# avr.net
KiCad netlist of a schematic drawn in EAGLE
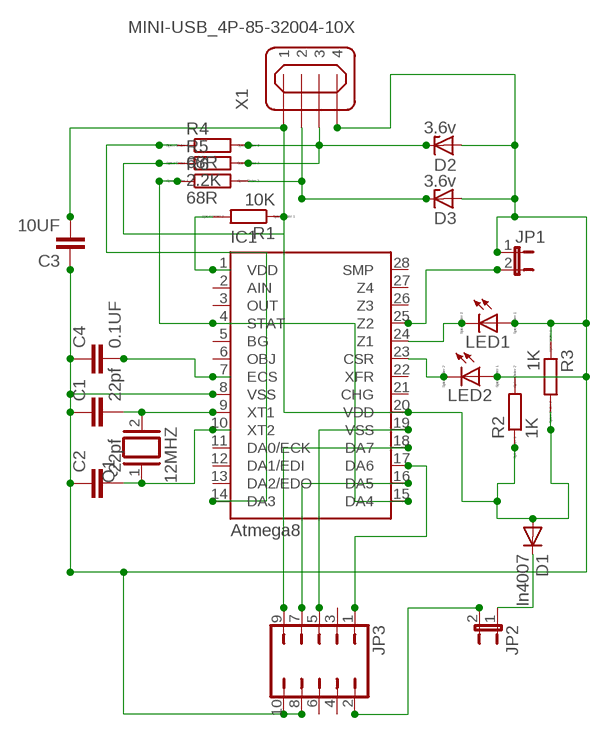
[diagram p0: schematic, sheet 1]

(export (version "E")
  (design (tool "Eeschema 10.0.6"))
  (components
    (comp (ref "C1")
      (value "22pf")
      (footprint "eagle-import:C2.5-3")
      (libsource (lib "eagle-import") (part "C2,5-3"))
    )
    (comp (ref "C2")
      (value "22pf")
      (footprint "eagle-import:C2.5-3")
      (libsource (lib "eagle-import") (part "C2,5-3"))
    )
    (comp (ref "C3")
      (value "10UF")
      (footprint "eagle-import:C2.5-3")
      (libsource (lib "eagle-import") (part "C2,5-3"))
    )
    (comp (ref "C4")
      (value "0.1UF")
      (footprint "eagle-import:C2.5-3")
      (libsource (lib "eagle-import") (part "C2,5-3"))
    )
    (comp (ref "D1")
      (value "In4007")
      (footprint "eagle-import:DO15-12")
      (libsource (lib "eagle-import") (part "1N5060GP"))
    )
    (comp (ref "D2")
      (value "3.6v")
      (footprint "eagle-import:DO41Z10")
      (libsource (lib "eagle-import") (part "1N4728"))
    )
    (comp (ref "D3")
      (value "3.6v")
      (footprint "eagle-import:DO41Z10")
      (libsource (lib "eagle-import") (part "1N4728"))
    )
    (comp (ref "IC1")
      (value "Atmega8")
      (footprint "eagle-import:DIL28-3")
      (libsource (lib "eagle-import") (part "QT9701BD"))
    )
    (comp (ref "JP1")
      (value "JP1E")
      (footprint "eagle-import:JP1")
      (libsource (lib "eagle-import") (part "JP1E"))
    )
    (comp (ref "JP2")
      (value "JP1E")
      (footprint "eagle-import:JP1")
      (libsource (lib "eagle-import") (part "JP1E"))
    )
    (comp (ref "JP3")
      (value "JP5Q")
      (footprint "eagle-import:JP5Q")
      (libsource (lib "eagle-import") (part "JP5Q"))
    )
    (comp (ref "LED1")
      (value "LED_ELD260")
      (footprint "eagle-import:LED_LD260")
      (libsource (lib "eagle-import") (part "LED_ELD260"))
    )
    (comp (ref "LED2")
      (value "LED_ELD260")
      (footprint "eagle-import:LED_LD260")
      (libsource (lib "eagle-import") (part "LED_ELD260"))
    )
    (comp (ref "Q1")
      (value "12MHZ")
      (footprint "eagle-import:QS")
      (libsource (lib "eagle-import") (part "XTAL/S"))
    )
    (comp (ref "R1")
      (value "10K")
      (footprint "eagle-import:0204_7")
      (libsource (lib "eagle-import") (part "R0204/7"))
    )
    (comp (ref "R2")
      (value "1K")
      (footprint "eagle-import:0204_7")
      (libsource (lib "eagle-import") (part "R0204/7"))
    )
    (comp (ref "R3")
      (value "1K")
      (footprint "eagle-import:0204_7")
      (libsource (lib "eagle-import") (part "R0204/7"))
    )
    (comp (ref "R4")
      (value "68R")
      (footprint "eagle-import:0204_7")
      (libsource (lib "eagle-import") (part "R0204/7"))
    )
    (comp (ref "R5")
      (value "2.2K")
      (footprint "eagle-import:0204_7")
      (libsource (lib "eagle-import") (part "R0204/7"))
    )
    (comp (ref "R6")
      (value "68R")
      (footprint "eagle-import:0204_7")
      (libsource (lib "eagle-import") (part "R0204/7"))
    )
    (comp (ref "X1")
      (value "MINI-USB_4P-85-32004-10X")
      (footprint "eagle-import:85-32004-10X")
      (libsource (lib "eagle-import") (part "MINI-USB_4P-85-32004-10X"))
    )
  )
  (nets
    (net (code "1") (name "Net-(C1-Pad1)") (class "Default")
      (node (ref "C1") (pin "1") (pinfunction "1_1") (pintype "passive"))
      (node (ref "C2") (pin "1") (pinfunction "1_1") (pintype "passive"))
      (node (ref "C3") (pin "1") (pinfunction "1_1") (pintype "passive"))
      (node (ref "C4") (pin "1") (pinfunction "1_1") (pintype "passive"))
      (node (ref "D2") (pin "A") (pinfunction "A_A") (pintype "passive"))
      (node (ref "D3") (pin "A") (pinfunction "A_A") (pintype "passive"))
      (node (ref "IC1") (pin "8") (pinfunction "VSS_8") (pintype "input"))
      (node (ref "JP1") (pin "1") (pinfunction "1_1") (pintype "passive"))
      (node (ref "JP3") (pin "10") (pinfunction "10_10") (pintype "passive"))
      (node (ref "JP3") (pin "8") (pinfunction "8_8") (pintype "passive"))
      (node (ref "LED1") (pin "A") (pinfunction "A_A") (pintype "passive"))
      (node (ref "LED2") (pin "A") (pinfunction "A_A") (pintype "passive"))
      (node (ref "R2") (pin "2") (pinfunction "2_2") (pintype "passive"))
      (node (ref "R3") (pin "1") (pinfunction "1_1") (pintype "passive"))
      (node (ref "X1") (pin "4") (pinfunction "4_4") (pintype "passive"))
    )
    (net (code "2") (name "Net-(C3-Pad2)") (class "Default")
      (node (ref "C3") (pin "2") (pinfunction "2_2") (pintype "passive"))
      (node (ref "D1") (pin "A") (pinfunction "A_A") (pintype "passive"))
      (node (ref "IC1") (pin "20") (pinfunction "VDD_20") (pintype "input"))
      (node (ref "R1") (pin "1") (pinfunction "1_1") (pintype "passive"))
      (node (ref "R2") (pin "1") (pinfunction "1_1") (pintype "passive"))
      (node (ref "R3") (pin "2") (pinfunction "2_2") (pintype "passive"))
      (node (ref "R5") (pin "1") (pinfunction "1_1") (pintype "passive"))
      (node (ref "X1") (pin "1") (pinfunction "1_1") (pintype "passive"))
    )
    (net (code "3") (name "Net-(D1-PadC)") (class "Default")
      (node (ref "D1") (pin "C") (pinfunction "C_C") (pintype "passive"))
      (node (ref "JP2") (pin "1") (pinfunction "1_1") (pintype "passive"))
    )
    (net (code "4") (name "Net-(D2-PadC)") (class "Default")
      (node (ref "D2") (pin "C") (pinfunction "C_C") (pintype "passive"))
      (node (ref "R4") (pin "2") (pinfunction "2_2") (pintype "passive"))
      (node (ref "R5") (pin "2") (pinfunction "2_2") (pintype "passive"))
      (node (ref "X1") (pin "3") (pinfunction "3_3") (pintype "passive"))
    )
    (net (code "5") (name "Net-(D3-PadC)") (class "Default")
      (node (ref "D3") (pin "C") (pinfunction "C_C") (pintype "passive"))
      (node (ref "R6") (pin "2") (pinfunction "2_2") (pintype "passive"))
      (node (ref "X1") (pin "2") (pinfunction "2_2") (pintype "passive"))
    )
    (net (code "6") (name "Net-(IC1-CSR)") (class "Default")
      (node (ref "IC1") (pin "23") (pinfunction "CSR_23") (pintype "output"))
      (node (ref "LED2") (pin "K") (pinfunction "C_K") (pintype "passive"))
    )
    (net (code "7") (name "Net-(IC1-DA3)") (class "Default")
      (node (ref "IC1") (pin "14") (pinfunction "DA3_14") (pintype "output"))
      (node (ref "R4") (pin "1") (pinfunction "1_1") (pintype "passive"))
    )
    (net (code "8") (name "Net-(IC1-DA4)") (class "Default")
      (node (ref "IC1") (pin "15") (pinfunction "DA4_15") (pintype "output"))
      (node (ref "IC1") (pin "4") (pinfunction "STAT_4") (pintype "output"))
      (node (ref "R6") (pin "1") (pinfunction "1_1") (pintype "passive"))
    )
    (net (code "9") (name "Net-(IC1-DA5)") (class "Default")
      (node (ref "IC1") (pin "16") (pinfunction "DA5_16") (pintype "output"))
      (node (ref "JP3") (pin "7") (pinfunction "7_7") (pintype "passive"))
    )
    (net (code "10") (name "Net-(IC1-DA6)") (class "Default")
      (node (ref "IC1") (pin "17") (pinfunction "DA6_17") (pintype "output"))
      (node (ref "JP3") (pin "1") (pinfunction "1_1") (pintype "passive"))
    )
    (net (code "11") (name "Net-(IC1-DA7)") (class "Default")
      (node (ref "IC1") (pin "18") (pinfunction "DA7_18") (pintype "output"))
      (node (ref "JP3") (pin "9") (pinfunction "9_9") (pintype "passive"))
    )
    (net (code "12") (name "Net-(IC1-ECS)") (class "Default")
      (node (ref "C4") (pin "2") (pinfunction "2_2") (pintype "passive"))
      (node (ref "IC1") (pin "7") (pinfunction "ECS_7") (pintype "output"))
    )
    (net (code "13") (name "Net-(IC1-VDD-Pad1)") (class "Default")
      (node (ref "IC1") (pin "1") (pinfunction "VDD_1") (pintype "input"))
      (node (ref "R1") (pin "2") (pinfunction "2_2") (pintype "passive"))
    )
    (net (code "14") (name "Net-(IC1-VSS-Pad19)") (class "Default")
      (node (ref "IC1") (pin "19") (pinfunction "VSS_19") (pintype "input"))
      (node (ref "JP3") (pin "5") (pinfunction "5_5") (pintype "passive"))
    )
    (net (code "15") (name "Net-(IC1-XT1)") (class "Default")
      (node (ref "C1") (pin "2") (pinfunction "2_2") (pintype "passive"))
      (node (ref "IC1") (pin "9") (pinfunction "XT1_9") (pintype "input"))
      (node (ref "Q1") (pin "2") (pinfunction "2_2") (pintype "passive"))
    )
    (net (code "16") (name "Net-(IC1-XT2)") (class "Default")
      (node (ref "C2") (pin "2") (pinfunction "2_2") (pintype "passive"))
      (node (ref "IC1") (pin "10") (pinfunction "XT2_10") (pintype "output"))
      (node (ref "Q1") (pin "1") (pinfunction "1_1") (pintype "passive"))
    )
    (net (code "17") (name "Net-(IC1-Z1)") (class "Default")
      (node (ref "IC1") (pin "24") (pinfunction "Z1_24") (pintype "output"))
      (node (ref "LED1") (pin "K") (pinfunction "C_K") (pintype "passive"))
    )
    (net (code "18") (name "Net-(IC1-Z2)") (class "Default")
      (node (ref "IC1") (pin "25") (pinfunction "Z2_25") (pintype "output"))
      (node (ref "JP1") (pin "2") (pinfunction "2_2") (pintype "passive"))
    )
    (net (code "19") (name "Net-(JP2-Pad2)") (class "Default")
      (node (ref "JP2") (pin "2") (pinfunction "2_2") (pintype "passive"))
      (node (ref "JP3") (pin "2") (pinfunction "2_2") (pintype "passive"))
    )
    (net (code "20") (name "unconnected-(IC1-AIN-Pad2)") (class "Default")
      (node (ref "IC1") (pin "2") (pinfunction "AIN_2") (pintype "input"))
    )
    (net (code "21") (name "unconnected-(IC1-BG-Pad5)") (class "Default")
      (node (ref "IC1") (pin "5") (pinfunction "BG_5") (pintype "input"))
    )
    (net (code "22") (name "unconnected-(IC1-CHG-Pad21)") (class "Default")
      (node (ref "IC1") (pin "21") (pinfunction "CHG_21") (pintype "output"))
    )
    (net (code "23") (name "unconnected-(IC1-DA0{slash}ECK-Pad11)") (class "Default")
      (node (ref "IC1") (pin "11") (pinfunction "DA0/ECK_11") (pintype "output"))
    )
    (net (code "24") (name "unconnected-(IC1-DA1{slash}EDI-Pad12)") (class "Default")
      (node (ref "IC1") (pin "12") (pinfunction "DA1/EDI_12") (pintype "output"))
    )
    (net (code "25") (name "unconnected-(IC1-DA2{slash}EDO-Pad13)") (class "Default")
      (node (ref "IC1") (pin "13") (pinfunction "DA2/EDO_13") (pintype "output"))
    )
    (net (code "26") (name "unconnected-(IC1-OBJ-Pad6)") (class "Default")
      (node (ref "IC1") (pin "6") (pinfunction "OBJ_6") (pintype "input"))
    )
    (net (code "27") (name "unconnected-(IC1-OUT-Pad3)") (class "Default")
      (node (ref "IC1") (pin "3") (pinfunction "OUT_3") (pintype "output"))
    )
    (net (code "28") (name "unconnected-(IC1-SMP-Pad28)") (class "Default")
      (node (ref "IC1") (pin "28") (pinfunction "SMP_28") (pintype "output"))
    )
    (net (code "29") (name "unconnected-(IC1-XFR-Pad22)") (class "Default")
      (node (ref "IC1") (pin "22") (pinfunction "XFR_22") (pintype "output"))
    )
    (net (code "30") (name "unconnected-(IC1-Z3-Pad26)") (class "Default")
      (node (ref "IC1") (pin "26") (pinfunction "Z3_26") (pintype "output"))
    )
    (net (code "31") (name "unconnected-(IC1-Z4-Pad27)") (class "Default")
      (node (ref "IC1") (pin "27") (pinfunction "Z4_27") (pintype "output"))
    )
    (net (code "32") (name "unconnected-(JP3-Pad3)") (class "Default")
      (node (ref "JP3") (pin "3") (pinfunction "3_3") (pintype "passive"))
    )
    (net (code "33") (name "unconnected-(JP3-Pad4)") (class "Default")
      (node (ref "JP3") (pin "4") (pinfunction "4_4") (pintype "passive"))
    )
    (net (code "34") (name "unconnected-(JP3-Pad6)") (class "Default")
      (node (ref "JP3") (pin "6") (pinfunction "6_6") (pintype "passive"))
    )
  )
)
